# USB-connector.net
KiCad netlist of a schematic drawn in Altium Designer
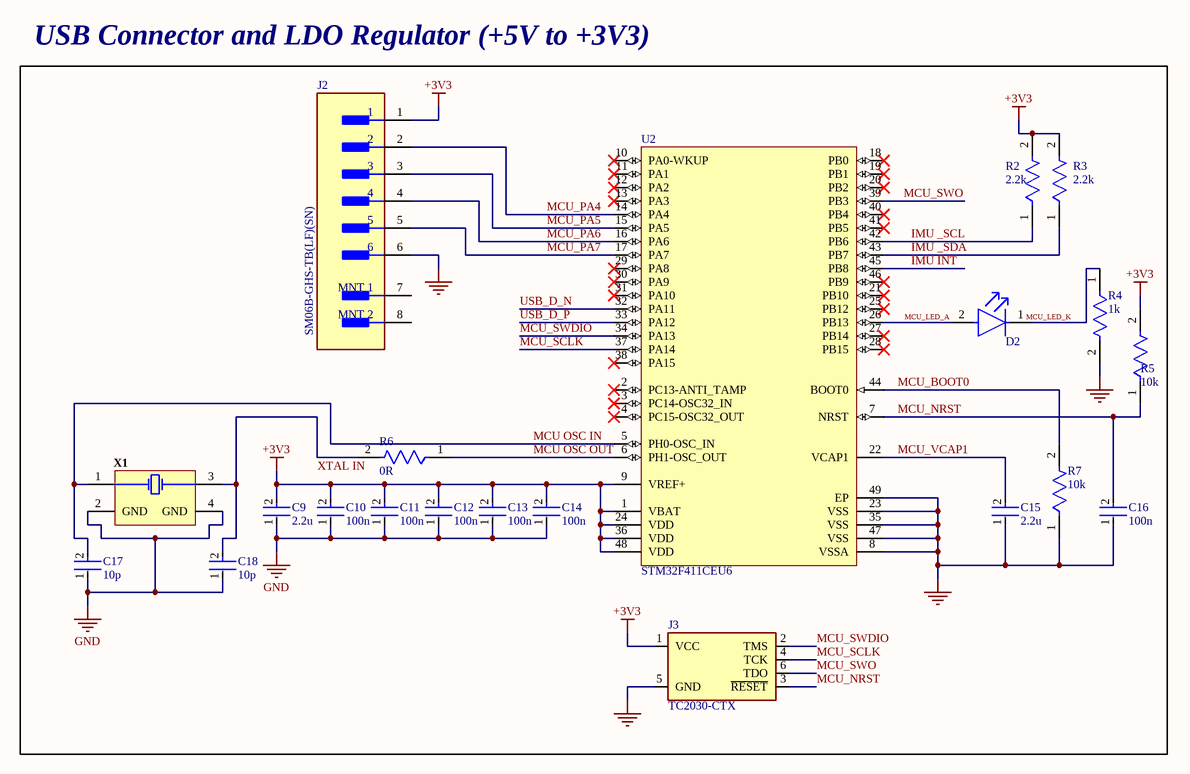
[diagram p0: USB-connector.SchDoc]

(export (version "E")
  (design (tool "Eeschema 10.0.6"))
  (components
    (comp (ref "C9")
      (value "2.2u")
      (footprint "FP-GRM15-MFG")
      (description "CAP CER 0.1UF 16V X7R 0402")
      (fields (field (name "MANUFACTURER PART NUMBER") "GRM155R71C104KA88D") (field (name "TOLERANCE") "10%"))
      (libsource (lib "Altium Content Vault") (part "236180d848d6139a670b325ea6854c9"))
    )
    (comp (ref "C10")
      (value "100n")
      (footprint "FP-GRM15-MFG")
      (description "CAP CER 0.1UF 16V X7R 0402")
      (fields (field (name "MANUFACTURER PART NUMBER") "GRM155R71C104KA88D") (field (name "TOLERANCE") "10%"))
      (libsource (lib "Altium Content Vault") (part "236180d848d6139a670b325ea6854c9"))
    )
    (comp (ref "C11")
      (value "100n")
      (footprint "FP-GRM15-MFG")
      (description "CAP CER 0.1UF 16V X7R 0402")
      (fields (field (name "MANUFACTURER PART NUMBER") "GRM155R71C104KA88D") (field (name "TOLERANCE") "10%"))
      (libsource (lib "Altium Content Vault") (part "236180d848d6139a670b325ea6854c9"))
    )
    (comp (ref "C12")
      (value "100n")
      (footprint "FP-GRM15-MFG")
      (description "CAP CER 0.1UF 16V X7R 0402")
      (fields (field (name "MANUFACTURER PART NUMBER") "GRM155R71C104KA88D") (field (name "TOLERANCE") "10%"))
      (libsource (lib "Altium Content Vault") (part "236180d848d6139a670b325ea6854c9"))
    )
    (comp (ref "C13")
      (value "100n")
      (footprint "FP-GRM15-MFG")
      (description "CAP CER 0.1UF 16V X7R 0402")
      (fields (field (name "MANUFACTURER PART NUMBER") "GRM155R71C104KA88D") (field (name "TOLERANCE") "10%"))
      (libsource (lib "Altium Content Vault") (part "236180d848d6139a670b325ea6854c9"))
    )
    (comp (ref "C14")
      (value "100n")
      (footprint "FP-GRM15-MFG")
      (description "CAP CER 0.1UF 16V X7R 0402")
      (fields (field (name "MANUFACTURER PART NUMBER") "GRM155R71C104KA88D") (field (name "TOLERANCE") "10%"))
      (libsource (lib "Altium Content Vault") (part "236180d848d6139a670b325ea6854c9"))
    )
    (comp (ref "C15")
      (value "2.2u")
      (footprint "FP-GRM15-MFG")
      (description "CAP CER 0.1UF 16V X7R 0402")
      (fields (field (name "MANUFACTURER PART NUMBER") "GRM155R71C104KA88D") (field (name "TOLERANCE") "10%"))
      (libsource (lib "Altium Content Vault") (part "236180d848d6139a670b325ea6854c9"))
    )
    (comp (ref "C16")
      (value "100n")
      (footprint "FP-GRM15-MFG")
      (description "CAP CER 0.1UF 16V X7R 0402")
      (fields (field (name "MANUFACTURER PART NUMBER") "GRM155R71C104KA88D") (field (name "TOLERANCE") "10%"))
      (libsource (lib "Altium Content Vault") (part "236180d848d6139a670b325ea6854c9"))
    )
    (comp (ref "C17")
      (value "10p")
      (footprint "FP-GRM15-MFG")
      (description "CAP CER 0.1UF 16V X7R 0402")
      (fields (field (name "MANUFACTURER PART NUMBER") "GRM155R71C104KA88D") (field (name "TOLERANCE") "10%"))
      (libsource (lib "Altium Content Vault") (part "236180d848d6139a670b325ea6854c9"))
    )
    (comp (ref "C18")
      (value "10p")
      (footprint "FP-GRM15-MFG")
      (description "CAP CER 0.1UF 16V X7R 0402")
      (fields (field (name "MANUFACTURER PART NUMBER") "GRM155R71C104KA88D") (field (name "TOLERANCE") "10%"))
      (libsource (lib "Altium Content Vault") (part "236180d848d6139a670b325ea6854c9"))
    )
    (comp (ref "D2")
      (value "SML-P11UTT86")
      (footprint "FP-SML-P11UTT86-MFG")
      (description "LED RED CLEAR 1006 SMD")
      (libsource (lib "Altium Content Vault") (part "8706943c75ba83719d021d2fdc84c58"))
    )
    (comp (ref "J2")
      (value "SM06B-GHS-TB(LF)(SN)")
      (footprint "FP-SM06B-GHS-TB_LF_SN-MFG")
      (description "CONN HEADER SMD R/A 6POS 1.25MM")
      (libsource (lib "Altium Content Vault") (part "ed24c53d9ba001d1a2a686240a95171"))
    )
    (comp (ref "J3")
      (value "TC2030-CTX")
      (footprint "TC2030-IDC-NL")
      (description "CortexÂ® Plug-Of-Nailsâ„¢ Adapter Cable")
      (fields (field (name "MF") "Tag-Connect LLC"))
      (libsource (lib "Akhila Prabodha") (part "TC2030-CTX"))
    )
    (comp (ref "R2")
      (value "2.2k")
      (footprint "FP-CRCW0402-e3-IPC_C")
      (description "RES Thick Film, 0Ω, 0.063W, 0402")
      (fields (field (name "TOLERANCE") "5%"))
      (libsource (lib "Altium Content Vault") (part "1029c3af85768c4190bb7ad29bc67b5"))
    )
    (comp (ref "R3")
      (value "2.2k")
      (footprint "FP-CRCW0402-e3-IPC_C")
      (description "RES Thick Film, 0Ω, 0.063W, 0402")
      (fields (field (name "TOLERANCE") "5%"))
      (libsource (lib "Altium Content Vault") (part "1029c3af85768c4190bb7ad29bc67b5"))
    )
    (comp (ref "R4")
      (value "1k")
      (footprint "FP-CRCW0402-e3-IPC_C")
      (description "RES Thick Film, 0Ω, 0.063W, 0402")
      (fields (field (name "TOLERANCE") "5%"))
      (libsource (lib "Altium Content Vault") (part "1029c3af85768c4190bb7ad29bc67b5"))
    )
    (comp (ref "R5")
      (value "10k")
      (footprint "FP-CRCW0402-e3-IPC_C")
      (description "RES Thick Film, 0Ω, 0.063W, 0402")
      (fields (field (name "TOLERANCE") "5%"))
      (libsource (lib "Altium Content Vault") (part "1029c3af85768c4190bb7ad29bc67b5"))
    )
    (comp (ref "R6")
      (value "0R")
      (footprint "FP-CRCW0402-e3-IPC_C")
      (description "RES Thick Film, 0Ω, 0.063W, 0402")
      (fields (field (name "TOLERANCE") "5%"))
      (libsource (lib "Altium Content Vault") (part "1029c3af85768c4190bb7ad29bc67b5"))
    )
    (comp (ref "R7")
      (value "10k")
      (footprint "FP-CRCW0402-e3-IPC_C")
      (description "RES Thick Film, 0Ω, 0.063W, 0402")
      (fields (field (name "TOLERANCE") "5%"))
      (libsource (lib "Altium Content Vault") (part "1029c3af85768c4190bb7ad29bc67b5"))
    )
    (comp (ref "U2")
      (value "STM32F411CEU6")
      (footprint "STM-UFQFPN48_L")
      (libsource (lib "Altium Content Vault") (part "MC-ARM-STM32F411-UFQFPN48"))
    )
    (comp (ref "X1")
      (value "TSX-3225 24.0000MF15X-AC3")
      (footprint "EPSON-TSX-3225_V")
      (description "MHz Range Crystal, 24 MHz, -40 to 85 degC, 4-Pin SMD, RoHS, Tape and Reel")
      (fields (field (name "TOLERANCE") "10PPM") (field (name "MANUFACTURER") "Epson"))
      (libsource (lib "Altium Content Vault") (part "XTAL-1-3-4"))
    )
  )
  (nets
    (net (code "1") (name "+3V3") (class "Default")
      (node (ref "C10") (pin "2") (pinfunction "2_2") (pintype "passive"))
      (node (ref "C11") (pin "2") (pinfunction "2_2") (pintype "passive"))
      (node (ref "C12") (pin "2") (pinfunction "2_2") (pintype "passive"))
      (node (ref "C13") (pin "2") (pinfunction "2_2") (pintype "passive"))
      (node (ref "C14") (pin "2") (pinfunction "2_2") (pintype "passive"))
      (node (ref "C9") (pin "2") (pinfunction "2_2") (pintype "passive"))
      (node (ref "J2") (pin "1") (pinfunction "1_1") (pintype "passive"))
      (node (ref "J3") (pin "1") (pinfunction "VCC_1") (pintype "bidirectional"))
      (node (ref "R2") (pin "2") (pinfunction "2_2") (pintype "passive"))
      (node (ref "R3") (pin "2") (pinfunction "2_2") (pintype "passive"))
      (node (ref "R5") (pin "2") (pinfunction "2_2") (pintype "passive"))
      (node (ref "U2") (pin "1") (pinfunction "VBAT_1") (pintype "power_in"))
      (node (ref "U2") (pin "24") (pinfunction "VDD_24") (pintype "power_in"))
      (node (ref "U2") (pin "36") (pinfunction "VDD_36") (pintype "power_in"))
      (node (ref "U2") (pin "48") (pinfunction "VDD_48") (pintype "power_in"))
      (node (ref "U2") (pin "9") (pinfunction "VREF+_9") (pintype "power_in"))
    )
    (net (code "2") (name "/IMU INT") (class "Default")
      (node (ref "U2") (pin "45") (pinfunction "PB8_45") (pintype "bidirectional"))
    )
    (net (code "3") (name "/IMU _SCL") (class "Default")
      (node (ref "R2") (pin "1") (pinfunction "1_1") (pintype "passive"))
      (node (ref "U2") (pin "42") (pinfunction "PB6_42") (pintype "bidirectional"))
    )
    (net (code "4") (name "/IMU _SDA") (class "Default")
      (node (ref "R3") (pin "1") (pinfunction "1_1") (pintype "passive"))
      (node (ref "U2") (pin "43") (pinfunction "PB7_43") (pintype "bidirectional"))
    )
    (net (code "5") (name "/MCU OSC IN") (class "Default")
      (node (ref "C17") (pin "2") (pinfunction "2_2") (pintype "passive"))
      (node (ref "U2") (pin "5") (pinfunction "PH0-OSC_IN_5") (pintype "bidirectional"))
      (node (ref "X1") (pin "1") (pinfunction "X1_1") (pintype "passive"))
    )
    (net (code "6") (name "/MCU OSC OUT") (class "Default")
      (node (ref "R6") (pin "1") (pinfunction "1_1") (pintype "passive"))
      (node (ref "U2") (pin "6") (pinfunction "PH1-OSC_OUT_6") (pintype "bidirectional"))
    )
    (net (code "7") (name "/MCU_BOOT0") (class "Default")
      (node (ref "R7") (pin "2") (pinfunction "2_2") (pintype "passive"))
      (node (ref "U2") (pin "44") (pinfunction "BOOT0_44") (pintype "input"))
    )
    (net (code "8") (name "/MCU_LED_A") (class "Default")
      (node (ref "D2") (pin "2") (pinfunction "A_2") (pintype "passive"))
      (node (ref "U2") (pin "26") (pinfunction "PB13_26") (pintype "bidirectional"))
    )
    (net (code "9") (name "/MCU_LED_K") (class "Default")
      (node (ref "D2") (pin "1") (pinfunction "C_1") (pintype "passive"))
      (node (ref "R4") (pin "1") (pinfunction "1_1") (pintype "passive"))
    )
    (net (code "10") (name "/MCU_NRST") (class "Default")
      (node (ref "C16") (pin "2") (pinfunction "2_2") (pintype "passive"))
      (node (ref "J3") (pin "3") (pinfunction "~{RESET}_3") (pintype "bidirectional"))
      (node (ref "R5") (pin "1") (pinfunction "1_1") (pintype "passive"))
      (node (ref "U2") (pin "7") (pinfunction "NRST_7") (pintype "bidirectional"))
    )
    (net (code "11") (name "/MCU_PA4") (class "Default")
      (node (ref "J2") (pin "2") (pinfunction "2_2") (pintype "passive"))
      (node (ref "U2") (pin "14") (pinfunction "PA4_14") (pintype "bidirectional"))
    )
    (net (code "12") (name "/MCU_PA5") (class "Default")
      (node (ref "J2") (pin "3") (pinfunction "3_3") (pintype "passive"))
      (node (ref "U2") (pin "15") (pinfunction "PA5_15") (pintype "bidirectional"))
    )
    (net (code "13") (name "/MCU_PA6") (class "Default")
      (node (ref "J2") (pin "4") (pinfunction "4_4") (pintype "passive"))
      (node (ref "U2") (pin "16") (pinfunction "PA6_16") (pintype "bidirectional"))
    )
    (net (code "14") (name "/MCU_PA7") (class "Default")
      (node (ref "J2") (pin "5") (pinfunction "5_5") (pintype "passive"))
      (node (ref "U2") (pin "17") (pinfunction "PA7_17") (pintype "bidirectional"))
    )
    (net (code "15") (name "/MCU_SCLK") (class "Default")
      (node (ref "J3") (pin "4") (pinfunction "TCK_4") (pintype "bidirectional"))
      (node (ref "U2") (pin "37") (pinfunction "PA14_37") (pintype "bidirectional"))
    )
    (net (code "16") (name "/MCU_SWDIO") (class "Default")
      (node (ref "J3") (pin "2") (pinfunction "TMS_2") (pintype "bidirectional"))
      (node (ref "U2") (pin "34") (pinfunction "PA13_34") (pintype "bidirectional"))
    )
    (net (code "17") (name "/MCU_SWO") (class "Default")
      (node (ref "J3") (pin "6") (pinfunction "TDO_6") (pintype "bidirectional"))
      (node (ref "U2") (pin "39") (pinfunction "PB3_39") (pintype "bidirectional"))
    )
    (net (code "18") (name "/MCU_VCAP1") (class "Default")
      (node (ref "C15") (pin "2") (pinfunction "2_2") (pintype "passive"))
      (node (ref "U2") (pin "22") (pinfunction "VCAP1_22") (pintype "passive"))
    )
    (net (code "19") (name "/USB_D_N") (class "Default")
      (node (ref "U2") (pin "32") (pinfunction "PA11_32") (pintype "bidirectional"))
    )
    (net (code "20") (name "/USB_D_P") (class "Default")
      (node (ref "U2") (pin "33") (pinfunction "PA12_33") (pintype "bidirectional"))
    )
    (net (code "21") (name "/XTAL IN") (class "Default")
      (node (ref "C18") (pin "2") (pinfunction "2_2") (pintype "passive"))
      (node (ref "R6") (pin "2") (pinfunction "2_2") (pintype "passive"))
      (node (ref "X1") (pin "3") (pinfunction "X2_3") (pintype "passive"))
    )
    (net (code "22") (name "GND") (class "Default")
      (node (ref "C10") (pin "1") (pinfunction "1_1") (pintype "passive"))
      (node (ref "C11") (pin "1") (pinfunction "1_1") (pintype "passive"))
      (node (ref "C12") (pin "1") (pinfunction "1_1") (pintype "passive"))
      (node (ref "C13") (pin "1") (pinfunction "1_1") (pintype "passive"))
      (node (ref "C14") (pin "1") (pinfunction "1_1") (pintype "passive"))
      (node (ref "C15") (pin "1") (pinfunction "1_1") (pintype "passive"))
      (node (ref "C16") (pin "1") (pinfunction "1_1") (pintype "passive"))
      (node (ref "C17") (pin "1") (pinfunction "1_1") (pintype "passive"))
      (node (ref "C18") (pin "1") (pinfunction "1_1") (pintype "passive"))
      (node (ref "C9") (pin "1") (pinfunction "1_1") (pintype "passive"))
      (node (ref "J2") (pin "6") (pinfunction "6_6") (pintype "passive"))
      (node (ref "J3") (pin "5") (pinfunction "GND_5") (pintype "bidirectional"))
      (node (ref "R4") (pin "2") (pinfunction "2_2") (pintype "passive"))
      (node (ref "R7") (pin "1") (pinfunction "1_1") (pintype "passive"))
      (node (ref "U2") (pin "23") (pinfunction "VSS_23") (pintype "power_in"))
      (node (ref "U2") (pin "35") (pinfunction "VSS_35") (pintype "power_in"))
      (node (ref "U2") (pin "47") (pinfunction "VSS_47") (pintype "power_in"))
      (node (ref "U2") (pin "49") (pinfunction "EP_49") (pintype "power_in"))
      (node (ref "U2") (pin "8") (pinfunction "VSSA_8") (pintype "power_in"))
      (node (ref "X1") (pin "2") (pinfunction "GND_2") (pintype "power_in"))
      (node (ref "X1") (pin "4") (pinfunction "GND_4") (pintype "power_in"))
    )
    (net (code "23") (name "unconnected-(J2-MNT_1-Pad7)") (class "Default")
      (node (ref "J2") (pin "7") (pinfunction "MNT_1_7") (pintype "passive"))
    )
    (net (code "24") (name "unconnected-(J2-MNT_2-Pad8)") (class "Default")
      (node (ref "J2") (pin "8") (pinfunction "MNT_2_8") (pintype "passive"))
    )
    (net (code "25") (name "unconnected-(U2-PA0-WKUP-Pad10)") (class "Default")
      (node (ref "U2") (pin "10") (pinfunction "PA0-WKUP_10") (pintype "bidirectional+no_connect"))
    )
    (net (code "26") (name "unconnected-(U2-PA1-Pad11)") (class "Default")
      (node (ref "U2") (pin "11") (pinfunction "PA1_11") (pintype "bidirectional+no_connect"))
    )
    (net (code "27") (name "unconnected-(U2-PA2-Pad12)") (class "Default")
      (node (ref "U2") (pin "12") (pinfunction "PA2_12") (pintype "bidirectional+no_connect"))
    )
    (net (code "28") (name "unconnected-(U2-PA3-Pad13)") (class "Default")
      (node (ref "U2") (pin "13") (pinfunction "PA3_13") (pintype "bidirectional+no_connect"))
    )
    (net (code "29") (name "unconnected-(U2-PA8-Pad29)") (class "Default")
      (node (ref "U2") (pin "29") (pinfunction "PA8_29") (pintype "bidirectional+no_connect"))
    )
    (net (code "30") (name "unconnected-(U2-PA9-Pad30)") (class "Default")
      (node (ref "U2") (pin "30") (pinfunction "PA9_30") (pintype "bidirectional+no_connect"))
    )
    (net (code "31") (name "unconnected-(U2-PA10-Pad31)") (class "Default")
      (node (ref "U2") (pin "31") (pinfunction "PA10_31") (pintype "bidirectional+no_connect"))
    )
    (net (code "32") (name "unconnected-(U2-PA15-Pad38)") (class "Default")
      (node (ref "U2") (pin "38") (pinfunction "PA15_38") (pintype "bidirectional+no_connect"))
    )
    (net (code "33") (name "unconnected-(U2-PB0-Pad18)") (class "Default")
      (node (ref "U2") (pin "18") (pinfunction "PB0_18") (pintype "bidirectional+no_connect"))
    )
    (net (code "34") (name "unconnected-(U2-PB1-Pad19)") (class "Default")
      (node (ref "U2") (pin "19") (pinfunction "PB1_19") (pintype "bidirectional+no_connect"))
    )
    (net (code "35") (name "unconnected-(U2-PB2-Pad20)") (class "Default")
      (node (ref "U2") (pin "20") (pinfunction "PB2_20") (pintype "bidirectional+no_connect"))
    )
    (net (code "36") (name "unconnected-(U2-PB4-Pad40)") (class "Default")
      (node (ref "U2") (pin "40") (pinfunction "PB4_40") (pintype "bidirectional+no_connect"))
    )
    (net (code "37") (name "unconnected-(U2-PB5-Pad41)") (class "Default")
      (node (ref "U2") (pin "41") (pinfunction "PB5_41") (pintype "bidirectional+no_connect"))
    )
    (net (code "38") (name "unconnected-(U2-PB9-Pad46)") (class "Default")
      (node (ref "U2") (pin "46") (pinfunction "PB9_46") (pintype "bidirectional+no_connect"))
    )
    (net (code "39") (name "unconnected-(U2-PB10-Pad21)") (class "Default")
      (node (ref "U2") (pin "21") (pinfunction "PB10_21") (pintype "bidirectional+no_connect"))
    )
    (net (code "40") (name "unconnected-(U2-PB12-Pad25)") (class "Default")
      (node (ref "U2") (pin "25") (pinfunction "PB12_25") (pintype "bidirectional+no_connect"))
    )
    (net (code "41") (name "unconnected-(U2-PB14-Pad27)") (class "Default")
      (node (ref "U2") (pin "27") (pinfunction "PB14_27") (pintype "bidirectional+no_connect"))
    )
    (net (code "42") (name "unconnected-(U2-PB15-Pad28)") (class "Default")
      (node (ref "U2") (pin "28") (pinfunction "PB15_28") (pintype "bidirectional+no_connect"))
    )
    (net (code "43") (name "unconnected-(U2-PC13-ANTI_TAMP-Pad2)") (class "Default")
      (node (ref "U2") (pin "2") (pinfunction "PC13-ANTI_TAMP_2") (pintype "bidirectional+no_connect"))
    )
    (net (code "44") (name "unconnected-(U2-PC14-OSC32_IN-Pad3)") (class "Default")
      (node (ref "U2") (pin "3") (pinfunction "PC14-OSC32_IN_3") (pintype "bidirectional+no_connect"))
    )
    (net (code "45") (name "unconnected-(U2-PC15-OSC32_OUT-Pad4)") (class "Default")
      (node (ref "U2") (pin "4") (pinfunction "PC15-OSC32_OUT_4") (pintype "bidirectional+no_connect"))
    )
  )
)
